# Trimble_Thunderbolt_Monitor_Shield_v1.net
KiCad netlist of a schematic drawn in EAGLE
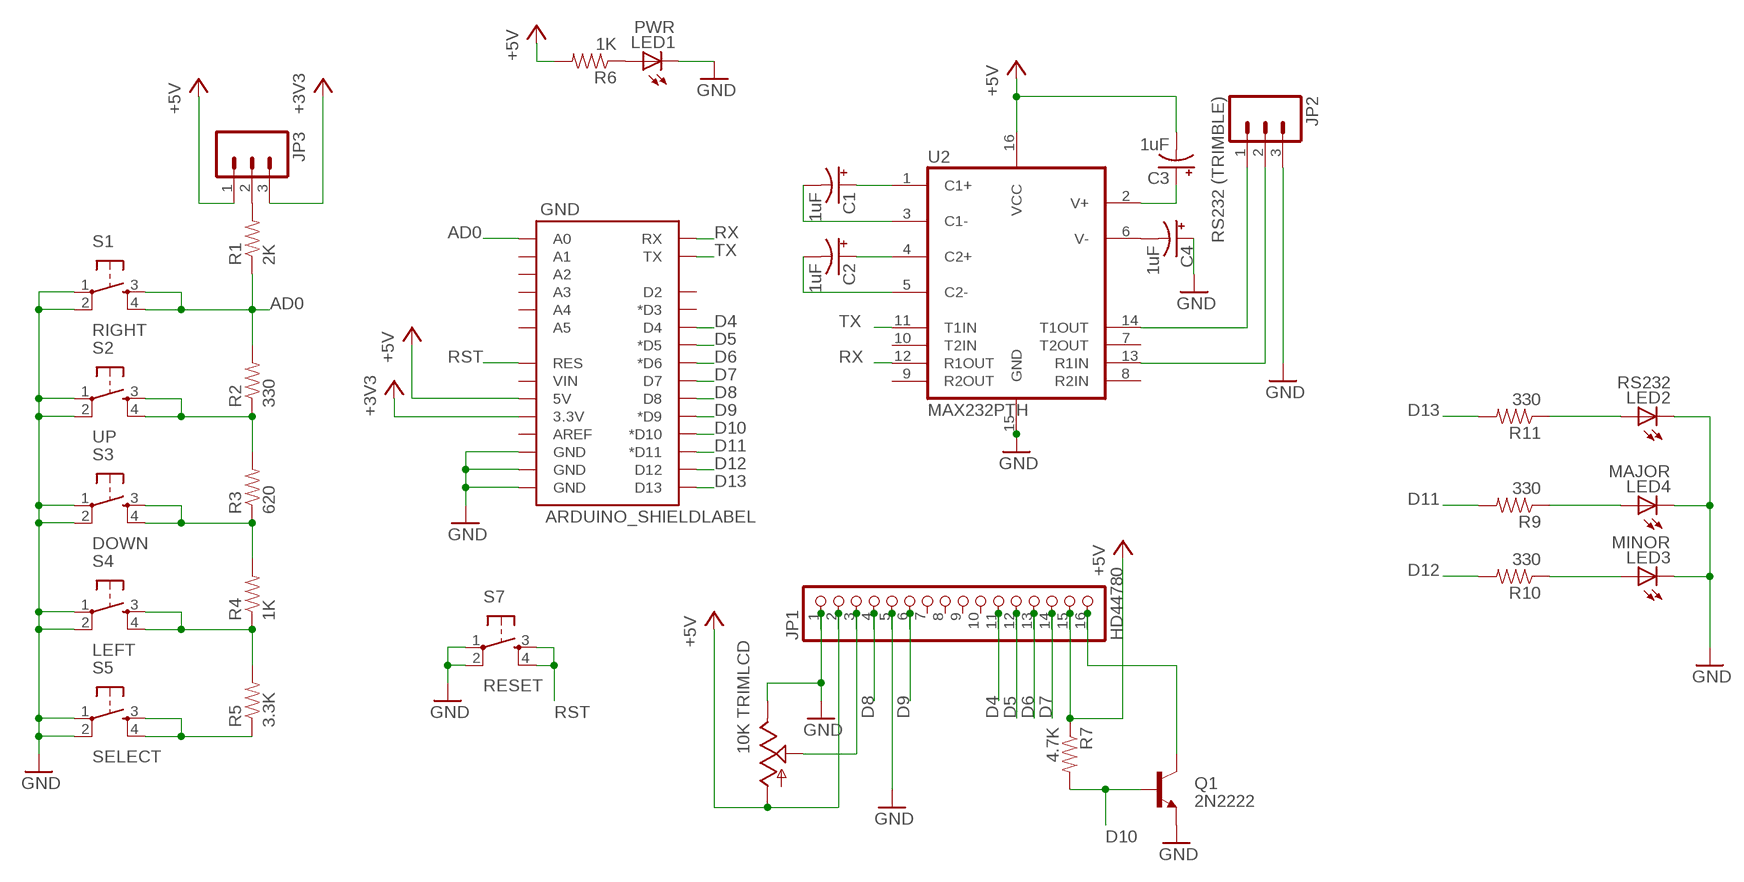
[diagram p0: schematic, sheet 1]

(export (version "E")
  (design (tool "Eeschema 10.0.6"))
  (components
    (comp (ref "C1")
      (value "1uF")
      (footprint "eagle-import:CPOL-RADIAL-10UF-25V")
      (libsource (lib "eagle-import") (part "CAP_POLPTH2"))
    )
    (comp (ref "C2")
      (value "1uF")
      (footprint "eagle-import:CPOL-RADIAL-10UF-25V")
      (libsource (lib "eagle-import") (part "CAP_POLPTH2"))
    )
    (comp (ref "C3")
      (value "1uF")
      (footprint "eagle-import:CPOL-RADIAL-10UF-25V")
      (libsource (lib "eagle-import") (part "CAP_POLPTH2"))
    )
    (comp (ref "C4")
      (value "1uF")
      (footprint "eagle-import:CPOL-RADIAL-10UF-25V")
      (libsource (lib "eagle-import") (part "CAP_POLPTH2"))
    )
    (comp (ref "GND")
      (value "ARDUINO_SHIELDLABEL")
      (footprint "eagle-import:DUEMILANOVE_SHIELD")
      (libsource (lib "eagle-import") (part "ARDUINO_SHIELDLABEL"))
    )
    (comp (ref "JP1")
      (value "HD44780")
      (footprint "eagle-import:1X16")
      (libsource (lib "eagle-import") (part "PINHD-1X16"))
    )
    (comp (ref "JP2")
      (value "RS232 (TRIMBLE)")
      (footprint "eagle-import:MOLEX-1X3")
      (libsource (lib "eagle-import") (part "M03POLAR"))
    )
    (comp (ref "JP3")
      (value "M03PTH")
      (footprint "eagle-import:1X03")
      (libsource (lib "eagle-import") (part "M03PTH"))
    )
    (comp (ref "LED1")
      (value "PWR")
      (footprint "eagle-import:LED5MM")
      (libsource (lib "eagle-import") (part "LED5MM"))
    )
    (comp (ref "LED2")
      (value "RS232")
      (footprint "eagle-import:LED5MM")
      (libsource (lib "eagle-import") (part "LED5MM"))
    )
    (comp (ref "LED3")
      (value "MINOR")
      (footprint "eagle-import:LED5MM")
      (libsource (lib "eagle-import") (part "LED5MM"))
    )
    (comp (ref "LED4")
      (value "MAJOR")
      (footprint "eagle-import:LED5MM")
      (libsource (lib "eagle-import") (part "LED5MM"))
    )
    (comp (ref "Q1")
      (value "2N2222")
      (footprint "eagle-import:TO-92-AMMO")
      (libsource (lib "eagle-import") (part "TRANSISTOR_NPNTO-92-AMMO"))
    )
    (comp (ref "R1")
      (value "2K")
      (footprint "eagle-import:AXIAL-0.3")
      (libsource (lib "eagle-import") (part "RESISTORAXIAL-0.3"))
    )
    (comp (ref "R2")
      (value "330")
      (footprint "eagle-import:AXIAL-0.3")
      (libsource (lib "eagle-import") (part "RESISTORAXIAL-0.3"))
    )
    (comp (ref "R3")
      (value "620")
      (footprint "eagle-import:AXIAL-0.3")
      (libsource (lib "eagle-import") (part "RESISTORAXIAL-0.3"))
    )
    (comp (ref "R4")
      (value "1K")
      (footprint "eagle-import:AXIAL-0.3")
      (libsource (lib "eagle-import") (part "RESISTORAXIAL-0.3"))
    )
    (comp (ref "R5")
      (value "3.3K")
      (footprint "eagle-import:AXIAL-0.3")
      (libsource (lib "eagle-import") (part "RESISTORAXIAL-0.3"))
    )
    (comp (ref "R6")
      (value "1K")
      (footprint "eagle-import:AXIAL-0.3")
      (libsource (lib "eagle-import") (part "RESISTORAXIAL-0.3"))
    )
    (comp (ref "R7")
      (value "4.7K")
      (footprint "eagle-import:AXIAL-0.3")
      (libsource (lib "eagle-import") (part "RESISTORAXIAL-0.3"))
    )
    (comp (ref "R9")
      (value "330")
      (footprint "eagle-import:AXIAL-0.3")
      (libsource (lib "eagle-import") (part "RESISTORAXIAL-0.3"))
    )
    (comp (ref "R10")
      (value "330")
      (footprint "eagle-import:AXIAL-0.3")
      (libsource (lib "eagle-import") (part "RESISTORAXIAL-0.3"))
    )
    (comp (ref "R11")
      (value "330")
      (footprint "eagle-import:AXIAL-0.3")
      (libsource (lib "eagle-import") (part "RESISTORAXIAL-0.3"))
    )
    (comp (ref "S1")
      (value "RIGHT")
      (footprint "eagle-import:TACTILE-PTH")
      (libsource (lib "eagle-import") (part "TAC_SWITCHPTH"))
    )
    (comp (ref "S2")
      (value "UP")
      (footprint "eagle-import:TACTILE-PTH")
      (libsource (lib "eagle-import") (part "TAC_SWITCHPTH"))
    )
    (comp (ref "S3")
      (value "DOWN")
      (footprint "eagle-import:TACTILE-PTH")
      (libsource (lib "eagle-import") (part "TAC_SWITCHPTH"))
    )
    (comp (ref "S4")
      (value "LEFT")
      (footprint "eagle-import:TACTILE-PTH")
      (libsource (lib "eagle-import") (part "TAC_SWITCHPTH"))
    )
    (comp (ref "S5")
      (value "SELECT")
      (footprint "eagle-import:TACTILE-PTH")
      (libsource (lib "eagle-import") (part "TAC_SWITCHPTH"))
    )
    (comp (ref "S7")
      (value "RESET")
      (footprint "eagle-import:TACTILE-PTH")
      (libsource (lib "eagle-import") (part "TAC_SWITCHPTH"))
    )
    (comp (ref "TRIMLCD")
      (value "10K")
      (footprint "eagle-import:3362U")
      (libsource (lib "eagle-import") (part "POT100K_3362U"))
    )
    (comp (ref "U2")
      (value "MAX232PTH")
      (footprint "eagle-import:DIL16")
      (libsource (lib "eagle-import") (part "MAX232PTH"))
    )
  )
  (nets
    (net (code "1") (name "+3V3") (class "Default")
      (node (ref "GND") (pin "3.3V") (pinfunction "3.3V_3.3V") (pintype "bidirectional"))
      (node (ref "JP3") (pin "3") (pinfunction "3_3") (pintype "passive"))
    )
    (net (code "2") (name "+5V") (class "Default")
      (node (ref "C3") (pin "2") (pinfunction "-_2") (pintype "passive"))
      (node (ref "GND") (pin "5V") (pinfunction "5V_5V") (pintype "bidirectional"))
      (node (ref "JP1") (pin "15") (pinfunction "15_15") (pintype "passive"))
      (node (ref "JP1") (pin "2") (pinfunction "2_2") (pintype "passive"))
      (node (ref "JP3") (pin "1") (pinfunction "1_1") (pintype "passive"))
      (node (ref "R6") (pin "P$2") (pinfunction "2_P$2") (pintype "passive"))
      (node (ref "R7") (pin "P$1") (pinfunction "1_P$1") (pintype "passive"))
      (node (ref "TRIMLCD") (pin "P$3") (pinfunction "A_P$3") (pintype "passive"))
      (node (ref "U2") (pin "16") (pinfunction "VCC_16") (pintype "bidirectional"))
    )
    (net (code "3") (name "/AD0") (class "Default")
      (node (ref "GND") (pin "A0") (pinfunction "A0_A0") (pintype "bidirectional"))
      (node (ref "R1") (pin "P$1") (pinfunction "1_P$1") (pintype "passive"))
      (node (ref "R2") (pin "P$2") (pinfunction "2_P$2") (pintype "passive"))
      (node (ref "S1") (pin "3") (pinfunction "3_3") (pintype "passive"))
      (node (ref "S1") (pin "4") (pinfunction "4_4") (pintype "passive"))
    )
    (net (code "4") (name "/D4") (class "Default")
      (node (ref "GND") (pin "D4") (pinfunction "D4_D4") (pintype "bidirectional"))
      (node (ref "JP1") (pin "11") (pinfunction "11_11") (pintype "passive"))
    )
    (net (code "5") (name "/D5") (class "Default")
      (node (ref "GND") (pin "D5") (pinfunction "*D5_D5") (pintype "bidirectional"))
      (node (ref "JP1") (pin "12") (pinfunction "12_12") (pintype "passive"))
    )
    (net (code "6") (name "/D6") (class "Default")
      (node (ref "GND") (pin "D6") (pinfunction "*D6_D6") (pintype "bidirectional"))
      (node (ref "JP1") (pin "13") (pinfunction "13_13") (pintype "passive"))
    )
    (net (code "7") (name "/D7") (class "Default")
      (node (ref "GND") (pin "D7") (pinfunction "D7_D7") (pintype "bidirectional"))
      (node (ref "JP1") (pin "14") (pinfunction "14_14") (pintype "passive"))
    )
    (net (code "8") (name "/D8") (class "Default")
      (node (ref "GND") (pin "D8") (pinfunction "D8_D8") (pintype "bidirectional"))
      (node (ref "JP1") (pin "4") (pinfunction "4_4") (pintype "passive"))
    )
    (net (code "9") (name "/D9") (class "Default")
      (node (ref "GND") (pin "D9") (pinfunction "*D9_D9") (pintype "bidirectional"))
      (node (ref "JP1") (pin "6") (pinfunction "6_6") (pintype "passive"))
    )
    (net (code "10") (name "/D10") (class "Default")
      (node (ref "GND") (pin "D10") (pinfunction "*D10_D10") (pintype "bidirectional"))
      (node (ref "Q1") (pin "2") (pinfunction "B_2") (pintype "passive"))
      (node (ref "R7") (pin "P$2") (pinfunction "2_P$2") (pintype "passive"))
    )
    (net (code "11") (name "/D11") (class "Default")
      (node (ref "GND") (pin "D11") (pinfunction "*D11_D11") (pintype "bidirectional"))
      (node (ref "R9") (pin "P$2") (pinfunction "2_P$2") (pintype "passive"))
    )
    (net (code "12") (name "/D12") (class "Default")
      (node (ref "GND") (pin "D12") (pinfunction "D12_D12") (pintype "bidirectional"))
      (node (ref "R10") (pin "P$2") (pinfunction "2_P$2") (pintype "passive"))
    )
    (net (code "13") (name "/D13") (class "Default")
      (node (ref "GND") (pin "D13") (pinfunction "D13_D13") (pintype "bidirectional"))
      (node (ref "R11") (pin "P$2") (pinfunction "2_P$2") (pintype "passive"))
    )
    (net (code "14") (name "/RST") (class "Default")
      (node (ref "GND") (pin "RES") (pinfunction "RES_RES") (pintype "bidirectional"))
      (node (ref "S7") (pin "3") (pinfunction "3_3") (pintype "passive"))
      (node (ref "S7") (pin "4") (pinfunction "4_4") (pintype "passive"))
    )
    (net (code "15") (name "/RX") (class "Default")
      (node (ref "GND") (pin "RX") (pinfunction "RX_RX") (pintype "bidirectional"))
      (node (ref "U2") (pin "12") (pinfunction "R1OUT_12") (pintype "output"))
    )
    (net (code "16") (name "/TX") (class "Default")
      (node (ref "GND") (pin "TX") (pinfunction "TX_TX") (pintype "bidirectional"))
      (node (ref "U2") (pin "11") (pinfunction "T1IN_11") (pintype "input"))
    )
    (net (code "17") (name "GND") (class "Default")
      (node (ref "C4") (pin "1") (pinfunction "+_1") (pintype "passive"))
      (node (ref "GND") (pin "GND@0") (pinfunction "GND_GND@0") (pintype "bidirectional"))
      (node (ref "GND") (pin "GND@1") (pinfunction "GND_GND@1") (pintype "bidirectional"))
      (node (ref "GND") (pin "GND@2") (pinfunction "GND_GND@2") (pintype "bidirectional"))
      (node (ref "JP1") (pin "1") (pinfunction "1_1") (pintype "passive"))
      (node (ref "JP1") (pin "5") (pinfunction "5_5") (pintype "passive"))
      (node (ref "JP2") (pin "3") (pinfunction "3_3") (pintype "passive"))
      (node (ref "LED1") (pin "K") (pinfunction "C_K") (pintype "passive"))
      (node (ref "LED2") (pin "K") (pinfunction "C_K") (pintype "passive"))
      (node (ref "LED3") (pin "K") (pinfunction "C_K") (pintype "passive"))
      (node (ref "LED4") (pin "K") (pinfunction "C_K") (pintype "passive"))
      (node (ref "Q1") (pin "1") (pinfunction "E_1") (pintype "passive"))
      (node (ref "S1") (pin "1") (pinfunction "1_1") (pintype "passive"))
      (node (ref "S1") (pin "2") (pinfunction "2_2") (pintype "passive"))
      (node (ref "S2") (pin "1") (pinfunction "1_1") (pintype "passive"))
      (node (ref "S2") (pin "2") (pinfunction "2_2") (pintype "passive"))
      (node (ref "S3") (pin "1") (pinfunction "1_1") (pintype "passive"))
      (node (ref "S3") (pin "2") (pinfunction "2_2") (pintype "passive"))
      (node (ref "S4") (pin "1") (pinfunction "1_1") (pintype "passive"))
      (node (ref "S4") (pin "2") (pinfunction "2_2") (pintype "passive"))
      (node (ref "S5") (pin "1") (pinfunction "1_1") (pintype "passive"))
      (node (ref "S5") (pin "2") (pinfunction "2_2") (pintype "passive"))
      (node (ref "S7") (pin "1") (pinfunction "1_1") (pintype "passive"))
      (node (ref "S7") (pin "2") (pinfunction "2_2") (pintype "passive"))
      (node (ref "TRIMLCD") (pin "P$1") (pinfunction "E_P$1") (pintype "passive"))
      (node (ref "U2") (pin "15") (pinfunction "GND_15") (pintype "bidirectional"))
    )
    (net (code "18") (name "Net-(C1-+)") (class "Default")
      (node (ref "C1") (pin "1") (pinfunction "+_1") (pintype "passive"))
      (node (ref "U2") (pin "1") (pinfunction "C1+_1") (pintype "bidirectional"))
    )
    (net (code "19") (name "Net-(C1--)") (class "Default")
      (node (ref "C1") (pin "2") (pinfunction "-_2") (pintype "passive"))
      (node (ref "U2") (pin "3") (pinfunction "C1-_3") (pintype "bidirectional"))
    )
    (net (code "20") (name "Net-(C2-+)") (class "Default")
      (node (ref "C2") (pin "1") (pinfunction "+_1") (pintype "passive"))
      (node (ref "U2") (pin "4") (pinfunction "C2+_4") (pintype "bidirectional"))
    )
    (net (code "21") (name "Net-(C2--)") (class "Default")
      (node (ref "C2") (pin "2") (pinfunction "-_2") (pintype "passive"))
      (node (ref "U2") (pin "5") (pinfunction "C2-_5") (pintype "bidirectional"))
    )
    (net (code "22") (name "Net-(C3-+)") (class "Default")
      (node (ref "C3") (pin "1") (pinfunction "+_1") (pintype "passive"))
      (node (ref "U2") (pin "2") (pinfunction "V+_2") (pintype "bidirectional"))
    )
    (net (code "23") (name "Net-(C4--)") (class "Default")
      (node (ref "C4") (pin "2") (pinfunction "-_2") (pintype "passive"))
      (node (ref "U2") (pin "6") (pinfunction "V-_6") (pintype "bidirectional"))
    )
    (net (code "24") (name "Net-(Q1-C)") (class "Default")
      (node (ref "JP1") (pin "16") (pinfunction "16_16") (pintype "passive"))
      (node (ref "Q1") (pin "3") (pinfunction "C_3") (pintype "passive"))
    )
    (net (code "25") (name "Net-(R1-2)") (class "Default")
      (node (ref "JP3") (pin "2") (pinfunction "2_2") (pintype "passive"))
      (node (ref "R1") (pin "P$2") (pinfunction "2_P$2") (pintype "passive"))
    )
    (net (code "26") (name "Net-(R2-1)") (class "Default")
      (node (ref "R2") (pin "P$1") (pinfunction "1_P$1") (pintype "passive"))
      (node (ref "R3") (pin "P$2") (pinfunction "2_P$2") (pintype "passive"))
      (node (ref "S2") (pin "3") (pinfunction "3_3") (pintype "passive"))
      (node (ref "S2") (pin "4") (pinfunction "4_4") (pintype "passive"))
    )
    (net (code "27") (name "Net-(R3-1)") (class "Default")
      (node (ref "R3") (pin "P$1") (pinfunction "1_P$1") (pintype "passive"))
      (node (ref "R4") (pin "P$2") (pinfunction "2_P$2") (pintype "passive"))
      (node (ref "S3") (pin "3") (pinfunction "3_3") (pintype "passive"))
      (node (ref "S3") (pin "4") (pinfunction "4_4") (pintype "passive"))
    )
    (net (code "28") (name "Net-(R4-1)") (class "Default")
      (node (ref "R4") (pin "P$1") (pinfunction "1_P$1") (pintype "passive"))
      (node (ref "R5") (pin "P$2") (pinfunction "2_P$2") (pintype "passive"))
      (node (ref "S4") (pin "3") (pinfunction "3_3") (pintype "passive"))
      (node (ref "S4") (pin "4") (pinfunction "4_4") (pintype "passive"))
    )
    (net (code "29") (name "Net-(R5-1)") (class "Default")
      (node (ref "R5") (pin "P$1") (pinfunction "1_P$1") (pintype "passive"))
      (node (ref "S5") (pin "3") (pinfunction "3_3") (pintype "passive"))
      (node (ref "S5") (pin "4") (pinfunction "4_4") (pintype "passive"))
    )
    (net (code "30") (name "Net-(R6-1)") (class "Default")
      (node (ref "LED1") (pin "A") (pinfunction "A_A") (pintype "passive"))
      (node (ref "R6") (pin "P$1") (pinfunction "1_P$1") (pintype "passive"))
    )
    (net (code "31") (name "Net-(R9-1)") (class "Default")
      (node (ref "LED4") (pin "A") (pinfunction "A_A") (pintype "passive"))
      (node (ref "R9") (pin "P$1") (pinfunction "1_P$1") (pintype "passive"))
    )
    (net (code "32") (name "Net-(R10-1)") (class "Default")
      (node (ref "LED3") (pin "A") (pinfunction "A_A") (pintype "passive"))
      (node (ref "R10") (pin "P$1") (pinfunction "1_P$1") (pintype "passive"))
    )
    (net (code "33") (name "Net-(R11-1)") (class "Default")
      (node (ref "LED2") (pin "A") (pinfunction "A_A") (pintype "passive"))
      (node (ref "R11") (pin "P$1") (pinfunction "1_P$1") (pintype "passive"))
    )
    (net (code "34") (name "Net-(TRIMLCD-S)") (class "Default")
      (node (ref "JP1") (pin "3") (pinfunction "3_3") (pintype "passive"))
      (node (ref "TRIMLCD") (pin "P$2") (pinfunction "S_P$2") (pintype "passive"))
    )
    (net (code "35") (name "Net-(U2-R1IN)") (class "Default")
      (node (ref "JP2") (pin "2") (pinfunction "2_2") (pintype "passive"))
      (node (ref "U2") (pin "13") (pinfunction "R1IN_13") (pintype "input"))
    )
    (net (code "36") (name "Net-(U2-T1OUT)") (class "Default")
      (node (ref "JP2") (pin "1") (pinfunction "1_1") (pintype "passive"))
      (node (ref "U2") (pin "14") (pinfunction "T1OUT_14") (pintype "output"))
    )
    (net (code "37") (name "unconnected-(GND-*D3-PadD3)") (class "Default")
      (node (ref "GND") (pin "D3") (pinfunction "*D3_D3") (pintype "bidirectional"))
    )
    (net (code "38") (name "unconnected-(GND-PadA1)") (class "Default")
      (node (ref "GND") (pin "A1") (pinfunction "A1_A1") (pintype "bidirectional"))
    )
    (net (code "39") (name "unconnected-(GND-PadA2)") (class "Default")
      (node (ref "GND") (pin "A2") (pinfunction "A2_A2") (pintype "bidirectional"))
    )
    (net (code "40") (name "unconnected-(GND-PadA3)") (class "Default")
      (node (ref "GND") (pin "A3") (pinfunction "A3_A3") (pintype "bidirectional"))
    )
    (net (code "41") (name "unconnected-(GND-PadA4)") (class "Default")
      (node (ref "GND") (pin "A4") (pinfunction "A4_A4") (pintype "bidirectional"))
    )
    (net (code "42") (name "unconnected-(GND-PadA5)") (class "Default")
      (node (ref "GND") (pin "A5") (pinfunction "A5_A5") (pintype "bidirectional"))
    )
    (net (code "43") (name "unconnected-(GND-PadAREF)") (class "Default")
      (node (ref "GND") (pin "AREF") (pinfunction "AREF_AREF") (pintype "bidirectional"))
    )
    (net (code "44") (name "unconnected-(GND-PadD2)") (class "Default")
      (node (ref "GND") (pin "D2") (pinfunction "D2_D2") (pintype "bidirectional"))
    )
    (net (code "45") (name "unconnected-(GND-PadVIN)") (class "Default")
      (node (ref "GND") (pin "VIN") (pinfunction "VIN_VIN") (pintype "bidirectional"))
    )
    (net (code "46") (name "unconnected-(JP1-Pad7)") (class "Default")
      (node (ref "JP1") (pin "7") (pinfunction "7_7") (pintype "passive"))
    )
    (net (code "47") (name "unconnected-(JP1-Pad8)") (class "Default")
      (node (ref "JP1") (pin "8") (pinfunction "8_8") (pintype "passive"))
    )
    (net (code "48") (name "unconnected-(JP1-Pad9)") (class "Default")
      (node (ref "JP1") (pin "9") (pinfunction "9_9") (pintype "passive"))
    )
    (net (code "49") (name "unconnected-(JP1-Pad10)") (class "Default")
      (node (ref "JP1") (pin "10") (pinfunction "10_10") (pintype "passive"))
    )
    (net (code "50") (name "unconnected-(U2-R2IN-Pad8)") (class "Default")
      (node (ref "U2") (pin "8") (pinfunction "R2IN_8") (pintype "input"))
    )
    (net (code "51") (name "unconnected-(U2-R2OUT-Pad9)") (class "Default")
      (node (ref "U2") (pin "9") (pinfunction "R2OUT_9") (pintype "output"))
    )
    (net (code "52") (name "unconnected-(U2-T2IN-Pad10)") (class "Default")
      (node (ref "U2") (pin "10") (pinfunction "T2IN_10") (pintype "input"))
    )
    (net (code "53") (name "unconnected-(U2-T2OUT-Pad7)") (class "Default")
      (node (ref "U2") (pin "7") (pinfunction "T2OUT_7") (pintype "output"))
    )
  )
)
